# MCU.net
KiCad netlist of a schematic drawn in Altium Designer
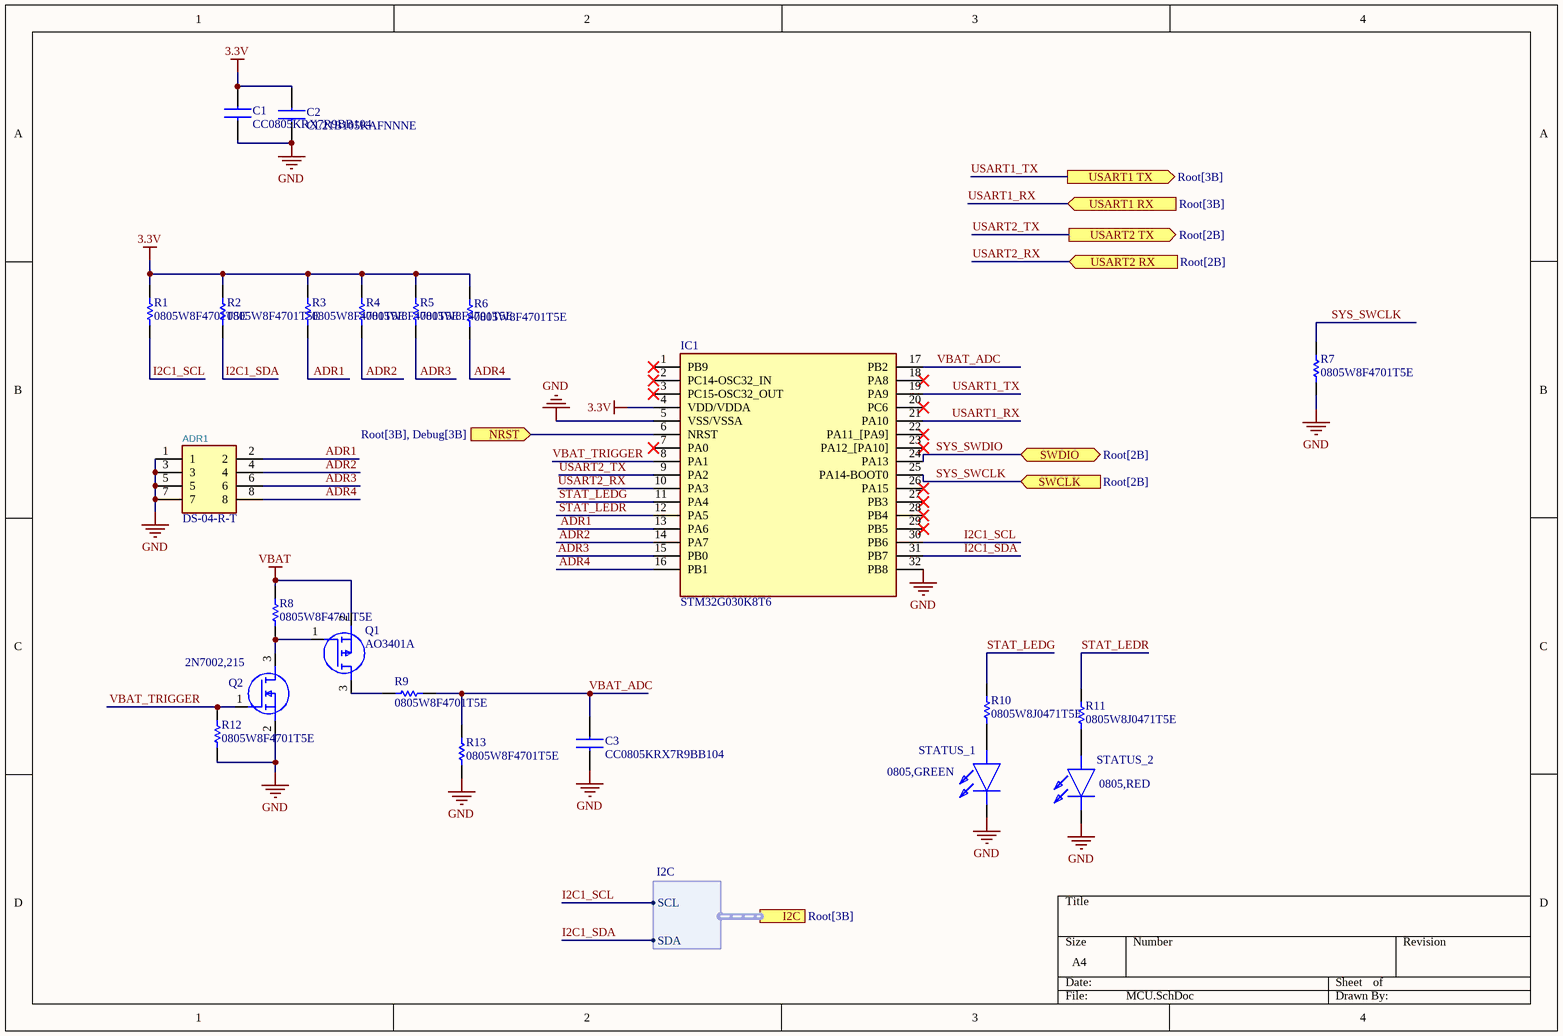
[diagram p0: MCU.SchDoc]

(export (version "E")
  (design (tool "Eeschema 10.0.6"))
  (components
    (comp (ref "ADR1")
      (value "DS-04-R-T")
      (footprint "DS-04-R-T")
      (description "-30℃~+85℃ 2.54mm 24V 25mA 3,000 Cycles 4 Red SPST Slide, Rocked Plugin,P=2.54mm DIP Switches ROHS")
      (fields (field (name "MANUFACTURER") "kangshen") (field (name "LCSC PART #") "C5123702"))
      (libsource (lib "MaUWB") (part "DS-04-R-T"))
    )
    (comp (ref "C1")
      (value "CC0805KRX7R9BB104")
      (footprint "CAPC2012X95N")
      (description "100nF, 0805, X7R")
      (fields (field (name "LCSC PART #") "C49678"))
      (libsource (lib "MaUWB") (part "CC0805KRX7R9BB104"))
    )
    (comp (ref "C2")
      (value "CL21B105KAFNNNE")
      (footprint "CAPC2012X135N")
      (description "1uF, 0805, X7R")
      (fields (field (name "LCSC PART #") "C28323") (field (name "MANU PART #") "CL21B105KBFNNNE"))
      (libsource (lib "MaUWB") (part "CL21B105KAFNNNE"))
    )
    (comp (ref "C3")
      (value "CC0805KRX7R9BB104")
      (footprint "CAPC2012X95N")
      (description "100nF, 0805, X7R")
      (fields (field (name "LCSC PART #") "C49678"))
      (libsource (lib "MaUWB") (part "CC0805KRX7R9BB104"))
    )
    (comp (ref "IC1")
      (value "STM32G030K8T6")
      (footprint "QFP80P900X900X160-32N")
      (fields (field (name "LCSC PART #") "C431631"))
      (libsource (lib "MaUWB") (part "STM32G030K8T6"))
    )
    (comp (ref "Q1")
      (value "AO3401A")
      (footprint "SOT95P280X125-3N - duplicate")
      (description "PMOS 4.2A SOT-23")
      (fields (field (name "LCSC PART #") "C21266"))
      (libsource (lib "MaUWB") (part "AO3401A"))
    )
    (comp (ref "Q2")
      (value "2N7002,215")
      (footprint "SOT95P230X110-3N")
      (description "MOSFET (N-Channel)")
      (fields (field (name "LCSC PART #") "C65189"))
      (libsource (lib "*") (part "2N7002,215"))
    )
    (comp (ref "R1")
      (value "0805W8F4701T5E")
      (footprint "RESC2013X65N")
      (description "4.7k 0805 1%")
      (fields (field (name "LCSC PART #") "C17673"))
      (libsource (lib "MaUWB") (part "0805W8F4701T5E"))
    )
    (comp (ref "R2")
      (value "0805W8F4701T5E")
      (footprint "RESC2013X65N")
      (description "4.7k 0805 1%")
      (fields (field (name "LCSC PART #") "C17673"))
      (libsource (lib "MaUWB") (part "0805W8F4701T5E"))
    )
    (comp (ref "R3")
      (value "0805W8F4701T5E")
      (footprint "RESC2013X65N")
      (description "4.7k 0805 1%")
      (fields (field (name "LCSC PART #") "C17673"))
      (libsource (lib "MaUWB") (part "0805W8F4701T5E"))
    )
    (comp (ref "R4")
      (value "0805W8F4701T5E")
      (footprint "RESC2013X65N")
      (description "4.7k 0805 1%")
      (fields (field (name "LCSC PART #") "C17673"))
      (libsource (lib "MaUWB") (part "0805W8F4701T5E"))
    )
    (comp (ref "R5")
      (value "0805W8F4701T5E")
      (footprint "RESC2013X65N")
      (description "4.7k 0805 1%")
      (fields (field (name "LCSC PART #") "C17673"))
      (libsource (lib "MaUWB") (part "0805W8F4701T5E"))
    )
    (comp (ref "R6")
      (value "0805W8F4701T5E")
      (footprint "RESC2013X65N")
      (description "4.7k 0805 1%")
      (fields (field (name "LCSC PART #") "C17673"))
      (libsource (lib "MaUWB") (part "0805W8F4701T5E"))
    )
    (comp (ref "R7")
      (value "0805W8F4701T5E")
      (footprint "RESC2013X65N")
      (description "4.7k 0805 1%")
      (fields (field (name "LCSC PART #") "C17673"))
      (libsource (lib "MaUWB") (part "0805W8F4701T5E"))
    )
    (comp (ref "R8")
      (value "0805W8F4701T5E")
      (footprint "RESC2013X65N")
      (description "4.7k 0805 1%")
      (fields (field (name "LCSC PART #") "C17673"))
      (libsource (lib "MaUWB") (part "0805W8F4701T5E"))
    )
    (comp (ref "R9")
      (value "0805W8F4701T5E")
      (footprint "RESC2013X65N")
      (description "4.7k 0805 1%")
      (fields (field (name "LCSC PART #") "C17673"))
      (libsource (lib "MaUWB") (part "0805W8F4701T5E"))
    )
    (comp (ref "R10")
      (value "0805W8J0471T5E")
      (footprint "RESC2013X65N - Duplicate")
      (description "470, 0805, 5%")
      (fields (field (name "LCSC PART #") "C17710") (field (name "MANU PART #") "0805W8F4700T5E"))
      (libsource (lib "MaUWB") (part "0805W8J0471T5E"))
    )
    (comp (ref "R11")
      (value "0805W8J0471T5E")
      (footprint "RESC2013X65N - Duplicate")
      (description "470, 0805, 5%")
      (fields (field (name "LCSC PART #") "C17710") (field (name "MANU PART #") "0805W8F4700T5E"))
      (libsource (lib "MaUWB") (part "0805W8J0471T5E"))
    )
    (comp (ref "R12")
      (value "0805W8F4701T5E")
      (footprint "RESC2013X65N")
      (description "4.7k 0805 1%")
      (fields (field (name "LCSC PART #") "C17673"))
      (libsource (lib "MaUWB") (part "0805W8F4701T5E"))
    )
    (comp (ref "R13")
      (value "0805W8F4701T5E")
      (footprint "RESC2013X65N")
      (description "4.7k 0805 1%")
      (fields (field (name "LCSC PART #") "C17673"))
      (libsource (lib "MaUWB") (part "0805W8F4701T5E"))
    )
    (comp (ref "STATUS_1")
      (value "0805,GREEN")
      (footprint "LEDC2012X120N")
      (description "Green 569nm LED Indication - Discrete 2.1V 0805 (2012 Metric)")
      (fields
        (field (name "MANUFACTURER_PART_NUMBER") "LTST-C170GKT")
        (field (name "MOUSER PART NUMBER") "859-LTST-C170GKT")
      )
      (libsource (lib "MaUWB") (part "LTST-C170GKT"))
    )
    (comp (ref "STATUS_2")
      (value "0805,RED")
      (footprint "LEDC2012X120N - Duplicate")
      (description "Red 631nm LED Indication - Discrete 2V 0805 (2012 Metric)")
      (fields
        (field (name "MANUFACTURER_PART_NUMBER") "LTST-C170KRKT")
        (field (name "MOUSER PART NUMBER") "859-LTST-C170KRKT")
      )
      (libsource (lib "MaUWB") (part "LTST-C170KRKT"))
    )
  )
  (nets
    (net (code "2") (name "/ADR1") (class "Default")
      (node (ref "ADR1") (pin "2") (pinfunction "2_2") (pintype "passive"))
      (node (ref "IC1") (pin "13") (pinfunction "PA6_13") (pintype "passive"))
      (node (ref "R3") (pin "1") (pinfunction "1_1") (pintype "passive"))
    )
    (net (code "3") (name "/ADR2") (class "Default")
      (node (ref "ADR1") (pin "4") (pinfunction "4_4") (pintype "passive"))
      (node (ref "IC1") (pin "14") (pinfunction "PA7_14") (pintype "passive"))
      (node (ref "R4") (pin "1") (pinfunction "1_1") (pintype "passive"))
    )
    (net (code "4") (name "/ADR3") (class "Default")
      (node (ref "ADR1") (pin "6") (pinfunction "6_6") (pintype "passive"))
      (node (ref "IC1") (pin "15") (pinfunction "PB0_15") (pintype "passive"))
      (node (ref "R5") (pin "1") (pinfunction "1_1") (pintype "passive"))
    )
    (net (code "5") (name "/ADR4") (class "Default")
      (node (ref "ADR1") (pin "8") (pinfunction "8_8") (pintype "passive"))
      (node (ref "IC1") (pin "16") (pinfunction "PB1_16") (pintype "passive"))
      (node (ref "R6") (pin "1") (pinfunction "1_1") (pintype "passive"))
    )
    (net (code "6") (name "/I2C1_SCL") (class "Default")
      (node (ref "IC1") (pin "30") (pinfunction "PB6_30") (pintype "passive"))
      (node (ref "R1") (pin "1") (pinfunction "1_1") (pintype "passive"))
    )
    (net (code "7") (name "/I2C1_SDA") (class "Default")
      (node (ref "IC1") (pin "31") (pinfunction "PB7_31") (pintype "passive"))
      (node (ref "R2") (pin "1") (pinfunction "1_1") (pintype "passive"))
    )
    (net (code "8") (name "/NRST") (class "Default")
      (node (ref "IC1") (pin "6") (pinfunction "NRST_6") (pintype "passive"))
    )
    (net (code "9") (name "/STAT_LEDG") (class "Default")
      (node (ref "IC1") (pin "11") (pinfunction "PA4_11") (pintype "passive"))
      (node (ref "R10") (pin "2") (pinfunction "2_2") (pintype "passive"))
    )
    (net (code "10") (name "/STAT_LEDR") (class "Default")
      (node (ref "IC1") (pin "12") (pinfunction "PA5_12") (pintype "passive"))
      (node (ref "R11") (pin "2") (pinfunction "2_2") (pintype "passive"))
    )
    (net (code "11") (name "/SYS_SWCLK") (class "Default")
      (node (ref "IC1") (pin "25") (pinfunction "PA14-BOOT0_25") (pintype "passive"))
      (node (ref "R7") (pin "2") (pinfunction "2_2") (pintype "passive"))
    )
    (net (code "12") (name "/SYS_SWDIO") (class "Default")
      (node (ref "IC1") (pin "24") (pinfunction "PA13_24") (pintype "passive"))
    )
    (net (code "13") (name "/USART1_RX") (class "Default")
      (node (ref "IC1") (pin "21") (pinfunction "PA10_21") (pintype "passive"))
    )
    (net (code "14") (name "/USART1_TX") (class "Default")
      (node (ref "IC1") (pin "19") (pinfunction "PA9_19") (pintype "passive"))
    )
    (net (code "15") (name "/USART2_RX") (class "Default")
      (node (ref "IC1") (pin "10") (pinfunction "PA3_10") (pintype "passive"))
    )
    (net (code "16") (name "/USART2_TX") (class "Default")
      (node (ref "IC1") (pin "9") (pinfunction "PA2_9") (pintype "passive"))
    )
    (net (code "17") (name "/VBAT_ADC") (class "Default")
      (node (ref "C3") (pin "2") (pinfunction "2_2") (pintype "passive"))
      (node (ref "IC1") (pin "17") (pinfunction "PB2_17") (pintype "passive"))
      (node (ref "R13") (pin "2") (pinfunction "2_2") (pintype "passive"))
      (node (ref "R9") (pin "1") (pinfunction "1_1") (pintype "passive"))
    )
    (net (code "18") (name "/VBAT_TRIGGER") (class "Default")
      (node (ref "IC1") (pin "8") (pinfunction "PA1_8") (pintype "passive"))
      (node (ref "Q2") (pin "1") (pinfunction "G_1") (pintype "passive"))
      (node (ref "R12") (pin "2") (pinfunction "2_2") (pintype "passive"))
    )
    (net (code "20") (name "3.3V") (class "Default")
      (node (ref "C1") (pin "2") (pinfunction "2_2") (pintype "passive"))
      (node (ref "C2") (pin "1") (pinfunction "1_1") (pintype "passive"))
      (node (ref "IC1") (pin "4") (pinfunction "VDD/VDDA_4") (pintype "passive"))
      (node (ref "R1") (pin "2") (pinfunction "2_2") (pintype "passive"))
      (node (ref "R2") (pin "2") (pinfunction "2_2") (pintype "passive"))
      (node (ref "R3") (pin "2") (pinfunction "2_2") (pintype "passive"))
      (node (ref "R4") (pin "2") (pinfunction "2_2") (pintype "passive"))
      (node (ref "R5") (pin "2") (pinfunction "2_2") (pintype "passive"))
      (node (ref "R6") (pin "2") (pinfunction "2_2") (pintype "passive"))
    )
    (net (code "21") (name "GND") (class "Default")
      (node (ref "ADR1") (pin "1") (pinfunction "1_1") (pintype "passive"))
      (node (ref "ADR1") (pin "3") (pinfunction "3_3") (pintype "passive"))
      (node (ref "ADR1") (pin "5") (pinfunction "5_5") (pintype "passive"))
      (node (ref "ADR1") (pin "7") (pinfunction "7_7") (pintype "passive"))
      (node (ref "C1") (pin "1") (pinfunction "1_1") (pintype "passive"))
      (node (ref "C2") (pin "2") (pinfunction "2_2") (pintype "passive"))
      (node (ref "C3") (pin "1") (pinfunction "1_1") (pintype "passive"))
      (node (ref "IC1") (pin "32") (pinfunction "PB8_32") (pintype "passive"))
      (node (ref "IC1") (pin "5") (pinfunction "VSS/VSSA_5") (pintype "passive"))
      (node (ref "Q2") (pin "2") (pinfunction "S_2") (pintype "passive"))
      (node (ref "R12") (pin "1") (pinfunction "1_1") (pintype "passive"))
      (node (ref "R13") (pin "1") (pinfunction "1_1") (pintype "passive"))
      (node (ref "R7") (pin "1") (pinfunction "1_1") (pintype "passive"))
      (node (ref "STATUS_1") (pin "1") (pinfunction "K_1") (pintype "passive"))
      (node (ref "STATUS_2") (pin "1") (pinfunction "K_1") (pintype "passive"))
    )
    (net (code "22") (name "Net-(Q1-D)") (class "Default")
      (node (ref "Q1") (pin "3") (pinfunction "D_3") (pintype "passive"))
      (node (ref "R9") (pin "2") (pinfunction "2_2") (pintype "passive"))
    )
    (net (code "23") (name "Net-(Q1-G)") (class "Default")
      (node (ref "Q1") (pin "1") (pinfunction "G_1") (pintype "passive"))
      (node (ref "Q2") (pin "3") (pinfunction "D_3") (pintype "passive"))
      (node (ref "R8") (pin "1") (pinfunction "1_1") (pintype "passive"))
    )
    (net (code "24") (name "Net-(STATUS_1-A)") (class "Default")
      (node (ref "R10") (pin "1") (pinfunction "1_1") (pintype "passive"))
      (node (ref "STATUS_1") (pin "2") (pinfunction "A_2") (pintype "passive"))
    )
    (net (code "25") (name "Net-(STATUS_2-A)") (class "Default")
      (node (ref "R11") (pin "1") (pinfunction "1_1") (pintype "passive"))
      (node (ref "STATUS_2") (pin "2") (pinfunction "A_2") (pintype "passive"))
    )
    (net (code "26") (name "VBAT") (class "Default")
      (node (ref "Q1") (pin "2") (pinfunction "S_2") (pintype "passive"))
      (node (ref "R8") (pin "2") (pinfunction "2_2") (pintype "passive"))
    )
    (net (code "27") (name "unconnected-(IC1-PA0-Pad7)") (class "Default")
      (node (ref "IC1") (pin "7") (pinfunction "PA0_7") (pintype "passive+no_connect"))
    )
    (net (code "28") (name "unconnected-(IC1-PA8-Pad18)") (class "Default")
      (node (ref "IC1") (pin "18") (pinfunction "PA8_18") (pintype "passive+no_connect"))
    )
    (net (code "29") (name "unconnected-(IC1-PA11_[PA9]-Pad22)") (class "Default")
      (node (ref "IC1") (pin "22") (pinfunction "PA11_[PA9]_22") (pintype "passive+no_connect"))
    )
    (net (code "30") (name "unconnected-(IC1-PA12_[PA10]-Pad23)") (class "Default")
      (node (ref "IC1") (pin "23") (pinfunction "PA12_[PA10]_23") (pintype "passive+no_connect"))
    )
    (net (code "31") (name "unconnected-(IC1-PA15-Pad26)") (class "Default")
      (node (ref "IC1") (pin "26") (pinfunction "PA15_26") (pintype "passive+no_connect"))
    )
    (net (code "32") (name "unconnected-(IC1-PB3-Pad27)") (class "Default")
      (node (ref "IC1") (pin "27") (pinfunction "PB3_27") (pintype "passive+no_connect"))
    )
    (net (code "33") (name "unconnected-(IC1-PB4-Pad28)") (class "Default")
      (node (ref "IC1") (pin "28") (pinfunction "PB4_28") (pintype "passive+no_connect"))
    )
    (net (code "34") (name "unconnected-(IC1-PB5-Pad29)") (class "Default")
      (node (ref "IC1") (pin "29") (pinfunction "PB5_29") (pintype "passive+no_connect"))
    )
    (net (code "35") (name "unconnected-(IC1-PB9-Pad1)") (class "Default")
      (node (ref "IC1") (pin "1") (pinfunction "PB9_1") (pintype "passive+no_connect"))
    )
    (net (code "36") (name "unconnected-(IC1-PC6-Pad20)") (class "Default")
      (node (ref "IC1") (pin "20") (pinfunction "PC6_20") (pintype "passive+no_connect"))
    )
    (net (code "37") (name "unconnected-(IC1-PC14-OSC32_IN-Pad2)") (class "Default")
      (node (ref "IC1") (pin "2") (pinfunction "PC14-OSC32_IN_2") (pintype "passive+no_connect"))
    )
    (net (code "38") (name "unconnected-(IC1-PC15-OSC32_OUT-Pad3)") (class "Default")
      (node (ref "IC1") (pin "3") (pinfunction "PC15-OSC32_OUT_3") (pintype "passive+no_connect"))
    )
  )
)
